# 03-AD9546_EdgeConnections_EEPROM.net
KiCad netlist of a schematic drawn in Altium Designer
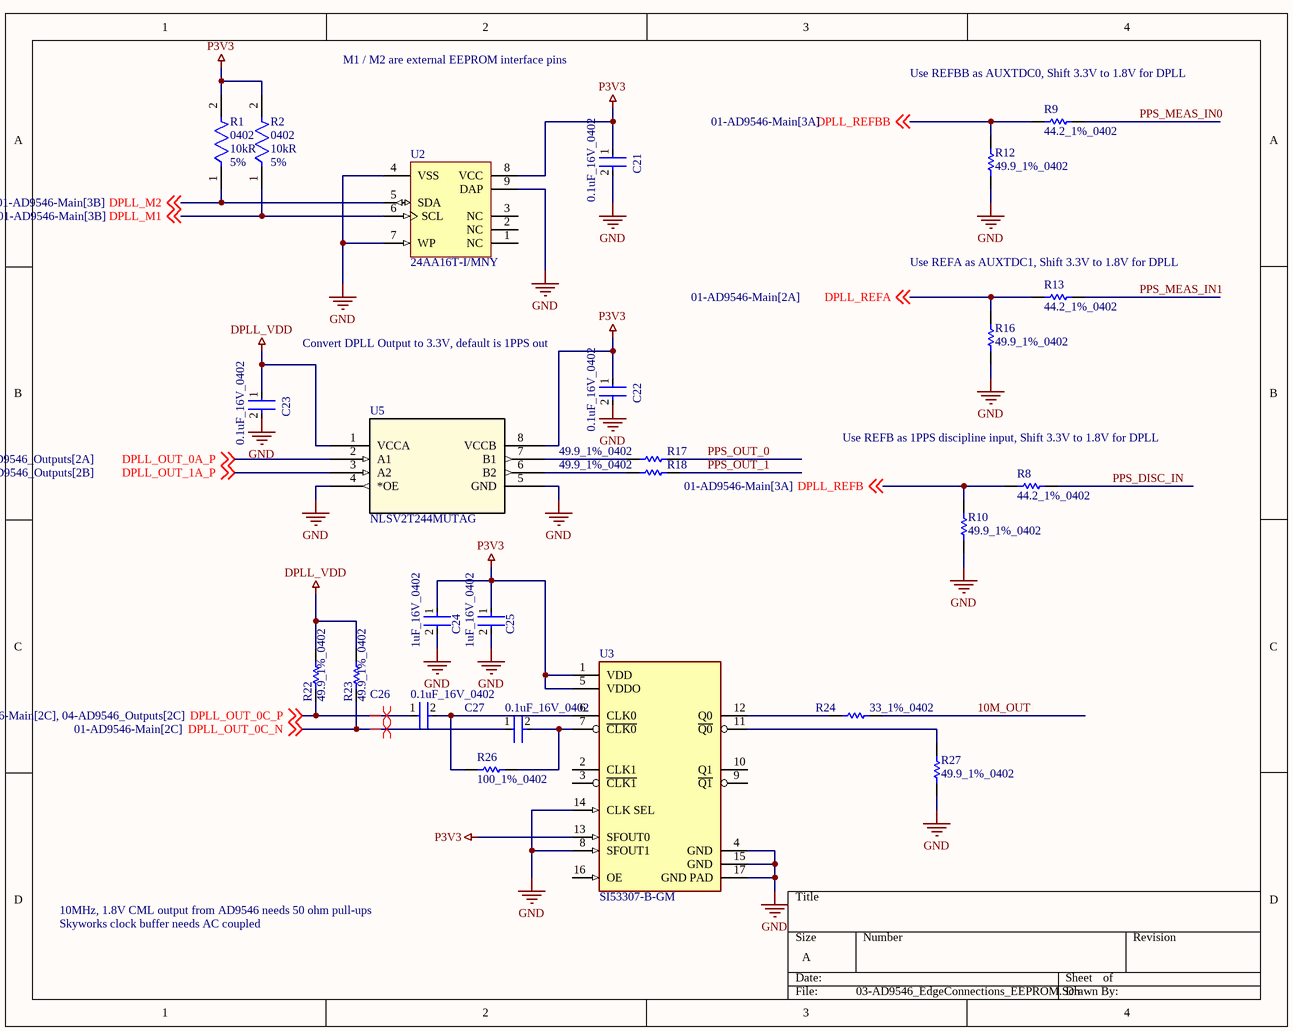
[diagram p0: 03-AD9546_EdgeConnections_EEPROM.SchDoc]

(export (version "E")
  (design (tool "Eeschema 10.0.6"))
  (components
    (comp (ref "C21")
      (value "0.1uF_16V_0402")
      (footprint "FP-GRM15-MFG")
      (description "CAP CER 0.1UF 16V X7R 0402")
      (fields (field (name "MANUFACTURER PART NUMBER") "GRM155R71C104KA88D") (field (name "TOLERANCE") "10%"))
      (libsource (lib "Altium Content Vault") (part "236180d848d6139a670b325ea6854c9"))
    )
    (comp (ref "C22")
      (value "0.1uF_16V_0402")
      (footprint "FP-GRM15-MFG")
      (description "CAP CER 0.1UF 16V X7R 0402")
      (fields (field (name "MANUFACTURER PART NUMBER") "GRM155R71C104KA88D") (field (name "TOLERANCE") "10%"))
      (libsource (lib "Altium Content Vault") (part "236180d848d6139a670b325ea6854c9"))
    )
    (comp (ref "C23")
      (value "0.1uF_16V_0402")
      (footprint "FP-GRM15-MFG")
      (description "CAP CER 0.1UF 16V X7R 0402")
      (fields (field (name "MANUFACTURER PART NUMBER") "GRM155R71C104KA88D") (field (name "TOLERANCE") "10%"))
      (libsource (lib "Altium Content Vault") (part "236180d848d6139a670b325ea6854c9"))
    )
    (comp (ref "C24")
      (value "1uF_16V_0402")
      (footprint "FP-0402-L_1_0_0_05-W_0_5-IPC_C")
      (description "None")
      (fields (field (name "TOLERANCE") "20%") (field (name "VOLTAGE") "16V"))
      (libsource (lib "Altium Content Vault") (part "b4654b650e69147ec39a6b967a45e02"))
    )
    (comp (ref "C25")
      (value "1uF_16V_0402")
      (footprint "FP-0402-L_1_0_0_05-W_0_5-IPC_C")
      (description "None")
      (fields (field (name "TOLERANCE") "20%") (field (name "VOLTAGE") "16V"))
      (libsource (lib "Altium Content Vault") (part "b4654b650e69147ec39a6b967a45e02"))
    )
    (comp (ref "C26")
      (value "0.1uF_16V_0402")
      (footprint "FP-GRM15-MFG")
      (description "CAP CER 0.1UF 16V X7R 0402")
      (fields (field (name "MANUFACTURER PART NUMBER") "GRM155R71C104KA88D") (field (name "TOLERANCE") "10%"))
      (libsource (lib "Altium Content Vault") (part "236180d848d6139a670b325ea6854c9"))
    )
    (comp (ref "C27")
      (value "0.1uF_16V_0402")
      (footprint "FP-GRM15-MFG")
      (description "CAP CER 0.1UF 16V X7R 0402")
      (fields (field (name "MANUFACTURER PART NUMBER") "GRM155R71C104KA88D") (field (name "TOLERANCE") "10%"))
      (libsource (lib "Altium Content Vault") (part "236180d848d6139a670b325ea6854c9"))
    )
    (comp (ref "R1")
      (value "CRCW040210K0JNED")
      (footprint "FP-CRCW0402-e3-IPC_B")
      (description "RES Thick Film, 10kΩ, 5%, 0.063W, 200ppm/°C, 0402")
      (fields
        (field (name "CASE/PACKAGE") "0402")
        (field (name "RESISTANCE") "10kR")
        (field (name "TOLERANCE") "5%")
      )
      (libsource (lib "Altium Content Vault") (part "1029c3af85768c4190bb7ad29bc67b5"))
    )
    (comp (ref "R2")
      (value "CRCW040210K0JNED")
      (footprint "FP-CRCW0402-e3-IPC_B")
      (description "RES Thick Film, 10kΩ, 5%, 0.063W, 200ppm/°C, 0402")
      (fields
        (field (name "CASE/PACKAGE") "0402")
        (field (name "RESISTANCE") "10kR")
        (field (name "TOLERANCE") "5%")
      )
      (libsource (lib "Altium Content Vault") (part "1029c3af85768c4190bb7ad29bc67b5"))
    )
    (comp (ref "R8")
      (value "44.2_1%_0402")
      (footprint "RESC1005X40X25LL05T05")
      (fields (field (name "MANUFACTURER") "Vishay Dale") (field (name "PART NUMBER") "CRCW040244R2FKED"))
      (libsource (lib "Altium Content Vault") (part "RES"))
    )
    (comp (ref "R9")
      (value "44.2_1%_0402")
      (footprint "RESC1005X40X25LL05T05")
      (fields (field (name "MANUFACTURER") "Vishay Dale") (field (name "PART NUMBER") "CRCW040244R2FKED"))
      (libsource (lib "Altium Content Vault") (part "RES"))
    )
    (comp (ref "R10")
      (value "49.9_1%_0402")
      (footprint "RESC1005X40X25NL05T05")
      (fields (field (name "MANUFACTURER") "Panasonic") (field (name "PART NUMBER") "ERJ-2RKF49R9X"))
      (libsource (lib "Altium Content Vault") (part "RES"))
    )
    (comp (ref "R12")
      (value "49.9_1%_0402")
      (footprint "RESC1005X40X25NL05T05")
      (fields (field (name "MANUFACTURER") "Panasonic") (field (name "PART NUMBER") "ERJ-2RKF49R9X"))
      (libsource (lib "Altium Content Vault") (part "RES"))
    )
    (comp (ref "R13")
      (value "44.2_1%_0402")
      (footprint "RESC1005X40X25LL05T05")
      (fields (field (name "MANUFACTURER") "Vishay Dale") (field (name "PART NUMBER") "CRCW040244R2FKED"))
      (libsource (lib "Altium Content Vault") (part "RES"))
    )
    (comp (ref "R16")
      (value "49.9_1%_0402")
      (footprint "RESC1005X40X25NL05T05")
      (fields (field (name "MANUFACTURER") "Panasonic") (field (name "PART NUMBER") "ERJ-2RKF49R9X"))
      (libsource (lib "Altium Content Vault") (part "RES"))
    )
    (comp (ref "R17")
      (value "49.9_1%_0402")
      (footprint "RESC1005X40X25NL05T05")
      (fields (field (name "MANUFACTURER") "Panasonic") (field (name "PART NUMBER") "ERJ-2RKF49R9X"))
      (libsource (lib "Altium Content Vault") (part "RES"))
    )
    (comp (ref "R18")
      (value "49.9_1%_0402")
      (footprint "RESC1005X40X25NL05T05")
      (fields (field (name "MANUFACTURER") "Panasonic") (field (name "PART NUMBER") "ERJ-2RKF49R9X"))
      (libsource (lib "Altium Content Vault") (part "RES"))
    )
    (comp (ref "R22")
      (value "49.9_1%_0402")
      (footprint "RESC1005X40X25NL05T05")
      (fields (field (name "MANUFACTURER") "Panasonic") (field (name "PART NUMBER") "ERJ-2RKF49R9X"))
      (libsource (lib "Altium Content Vault") (part "RES"))
    )
    (comp (ref "R23")
      (value "49.9_1%_0402")
      (footprint "RESC1005X40X25NL05T05")
      (fields (field (name "MANUFACTURER") "Panasonic") (field (name "PART NUMBER") "ERJ-2RKF49R9X"))
      (libsource (lib "Altium Content Vault") (part "RES"))
    )
    (comp (ref "R24")
      (value "33_1%_0402")
      (footprint "RESC1005X40X25LL05T10")
      (fields (field (name "PART NUMBER") "RC0402FR-0733RL") (field (name "MANUFACTURER") "Yageo / Phycomp"))
      (libsource (lib "Altium Content Vault") (part "RES"))
    )
    (comp (ref "R26")
      (value "100_1%_0402")
      (footprint "RESC1005X40X25ML05T10")
      (fields (field (name "PART NUMBER") "RC0402FR-07100RL") (field (name "MANUFACTURER") "Yageo / Phycomp"))
      (libsource (lib "Altium Content Vault") (part "RES"))
    )
    (comp (ref "R27")
      (value "49.9_1%_0402")
      (footprint "RESC1005X40X25NL05T05")
      (fields (field (name "MANUFACTURER") "Panasonic") (field (name "PART NUMBER") "ERJ-2RKF49R9X"))
      (libsource (lib "Altium Content Vault") (part "RES"))
    )
    (comp (ref "U2")
      (value "24AA16T-I/MNY")
      (footprint "TDFN-MN8")
      (libsource (lib "Altium Content Vault") (part "MEM-SEEPROM-24AA08-IL9"))
    )
    (comp (ref "U3")
      (value "SI53307-B-GM")
      (footprint "FP-SI53307-B-GM-MFG")
      (description "Clock Fanout Buffer (Distribution), Multiplexer IC 2:4 725MHz 16-VFQFN Exposed Pad")
      (fields (field (name "OCTOPART") "https://octopart.com/si53307-b-gm-silicon+labs-51374320"))
      (libsource (lib "Altium Content Vault") (part "8366162297a72c4edb5e5ae86e4b614"))
    )
    (comp (ref "U5")
      (value "NLSV2T244MUTAG")
      (footprint "UDFN8_1P20X1P80_ONS")
      (description "No Description Available")
      (fields (field (name "COPYRIGHT") "Copyright (C) 2023 Ultra Librarian. All rights reserved."))
      (libsource (lib "NLSV2T244MUTAG") (part "NLSV2T244MUTAG"))
    )
  )
  (nets
    (net (code "1") (name "/10M_OUT") (class "Default")
      (node (ref "R24") (pin "2") (pinfunction "2_2") (pintype "passive"))
    )
    (net (code "2") (name "/PPS_DISC_IN") (class "Default")
      (node (ref "R8") (pin "2") (pinfunction "2_2") (pintype "passive"))
    )
    (net (code "3") (name "/PPS_MEAS_IN0") (class "Default")
      (node (ref "R9") (pin "2") (pinfunction "2_2") (pintype "passive"))
    )
    (net (code "4") (name "/PPS_MEAS_IN1") (class "Default")
      (node (ref "R13") (pin "2") (pinfunction "2_2") (pintype "passive"))
    )
    (net (code "5") (name "/PPS_OUT_0") (class "Default")
      (node (ref "R17") (pin "1") (pinfunction "1_1") (pintype "passive"))
    )
    (net (code "6") (name "/PPS_OUT_1") (class "Default")
      (node (ref "R18") (pin "1") (pinfunction "1_1") (pintype "passive"))
    )
    (net (code "7") (name "DPLL_M1") (class "Default")
      (node (ref "R2") (pin "1") (pinfunction "1_1") (pintype "passive"))
      (node (ref "U2") (pin "6") (pinfunction "SCL_6") (pintype "input"))
    )
    (net (code "8") (name "DPLL_M2") (class "Default")
      (node (ref "R1") (pin "1") (pinfunction "1_1") (pintype "passive"))
      (node (ref "U2") (pin "5") (pinfunction "SDA_5") (pintype "bidirectional"))
    )
    (net (code "9") (name "DPLL_OUT_0A_P") (class "Default")
      (node (ref "U5") (pin "2") (pinfunction "A1_2") (pintype "input"))
    )
    (net (code "10") (name "DPLL_OUT_0C_N") (class "Default")
      (node (ref "C27") (pin "1") (pinfunction "1_1") (pintype "passive"))
      (node (ref "R23") (pin "2") (pinfunction "2_2") (pintype "passive"))
    )
    (net (code "11") (name "DPLL_OUT_0C_P") (class "Default")
      (node (ref "C26") (pin "1") (pinfunction "1_1") (pintype "passive"))
      (node (ref "R22") (pin "2") (pinfunction "2_2") (pintype "passive"))
    )
    (net (code "12") (name "DPLL_OUT_1A_P") (class "Default")
      (node (ref "U5") (pin "3") (pinfunction "A2_3") (pintype "input"))
    )
    (net (code "13") (name "DPLL_REFA") (class "Default")
      (node (ref "R13") (pin "1") (pinfunction "1_1") (pintype "passive"))
      (node (ref "R16") (pin "2") (pinfunction "2_2") (pintype "passive"))
    )
    (net (code "14") (name "DPLL_REFB") (class "Default")
      (node (ref "R10") (pin "2") (pinfunction "2_2") (pintype "passive"))
      (node (ref "R8") (pin "1") (pinfunction "1_1") (pintype "passive"))
    )
    (net (code "15") (name "DPLL_REFBB") (class "Default")
      (node (ref "R12") (pin "2") (pinfunction "2_2") (pintype "passive"))
      (node (ref "R9") (pin "1") (pinfunction "1_1") (pintype "passive"))
    )
    (net (code "16") (name "DPLL_VDD") (class "Default")
      (node (ref "C23") (pin "1") (pinfunction "1_1") (pintype "passive"))
      (node (ref "R22") (pin "1") (pinfunction "1_1") (pintype "passive"))
      (node (ref "R23") (pin "1") (pinfunction "1_1") (pintype "passive"))
      (node (ref "U5") (pin "1") (pinfunction "VCCA_1") (pintype "power_in"))
    )
    (net (code "17") (name "GND") (class "Default")
      (node (ref "C21") (pin "2") (pinfunction "2_2") (pintype "passive"))
      (node (ref "C22") (pin "2") (pinfunction "2_2") (pintype "passive"))
      (node (ref "C23") (pin "2") (pinfunction "2_2") (pintype "passive"))
      (node (ref "C24") (pin "2") (pinfunction "2_2") (pintype "passive"))
      (node (ref "C25") (pin "2") (pinfunction "2_2") (pintype "passive"))
      (node (ref "R10") (pin "1") (pinfunction "1_1") (pintype "passive"))
      (node (ref "R12") (pin "1") (pinfunction "1_1") (pintype "passive"))
      (node (ref "R16") (pin "1") (pinfunction "1_1") (pintype "passive"))
      (node (ref "R27") (pin "2") (pinfunction "2_2") (pintype "passive"))
      (node (ref "U2") (pin "4") (pinfunction "VSS_4") (pintype "power_in"))
      (node (ref "U2") (pin "7") (pinfunction "WP_7") (pintype "input"))
      (node (ref "U2") (pin "9") (pinfunction "DAP_9") (pintype "power_in"))
      (node (ref "U3") (pin "14") (pinfunction "CLK_SEL_14") (pintype "input"))
      (node (ref "U3") (pin "15") (pinfunction "GND_15") (pintype "power_in"))
      (node (ref "U3") (pin "17") (pinfunction "GND_PAD_17") (pintype "power_in"))
      (node (ref "U3") (pin "4") (pinfunction "GND_4") (pintype "power_in"))
      (node (ref "U3") (pin "8") (pinfunction "SFOUT1_8") (pintype "input"))
      (node (ref "U5") (pin "4") (pinfunction "*OE_4") (pintype "output"))
      (node (ref "U5") (pin "5") (pinfunction "GND_5") (pintype "power_in"))
    )
    (net (code "18") (name "Net-(U3-CLK0)") (class "Default")
      (node (ref "C26") (pin "2") (pinfunction "2_2") (pintype "passive"))
      (node (ref "R26") (pin "1") (pinfunction "1_1") (pintype "passive"))
      (node (ref "U3") (pin "6") (pinfunction "CLK0_6") (pintype "passive"))
    )
    (net (code "19") (name "Net-(U3-Q0)") (class "Default")
      (node (ref "R24") (pin "1") (pinfunction "1_1") (pintype "passive"))
      (node (ref "U3") (pin "12") (pinfunction "Q0_12") (pintype "passive"))
    )
    (net (code "20") (name "Net-(U3-~{CLK0})") (class "Default")
      (node (ref "C27") (pin "2") (pinfunction "2_2") (pintype "passive"))
      (node (ref "R26") (pin "2") (pinfunction "2_2") (pintype "passive"))
      (node (ref "U3") (pin "7") (pinfunction "~{CLK0}_7") (pintype "passive"))
    )
    (net (code "21") (name "Net-(U3-~{Q0})") (class "Default")
      (node (ref "R27") (pin "1") (pinfunction "1_1") (pintype "passive"))
      (node (ref "U3") (pin "11") (pinfunction "~{Q0}_11") (pintype "passive"))
    )
    (net (code "22") (name "Net-(U5-B1)") (class "Default")
      (node (ref "R17") (pin "2") (pinfunction "2_2") (pintype "passive"))
      (node (ref "U5") (pin "7") (pinfunction "B1_7") (pintype "output"))
    )
    (net (code "23") (name "Net-(U5-B2)") (class "Default")
      (node (ref "R18") (pin "2") (pinfunction "2_2") (pintype "passive"))
      (node (ref "U5") (pin "6") (pinfunction "B2_6") (pintype "output"))
    )
    (net (code "24") (name "P3V3") (class "Default")
      (node (ref "C21") (pin "1") (pinfunction "1_1") (pintype "passive"))
      (node (ref "C22") (pin "1") (pinfunction "1_1") (pintype "passive"))
      (node (ref "C24") (pin "1") (pinfunction "1_1") (pintype "passive"))
      (node (ref "C25") (pin "1") (pinfunction "1_1") (pintype "passive"))
      (node (ref "R1") (pin "2") (pinfunction "2_2") (pintype "passive"))
      (node (ref "R2") (pin "2") (pinfunction "2_2") (pintype "passive"))
      (node (ref "U2") (pin "8") (pinfunction "VCC_8") (pintype "power_in"))
      (node (ref "U3") (pin "1") (pinfunction "VDD_1") (pintype "power_in"))
      (node (ref "U3") (pin "13") (pinfunction "SFOUT0_13") (pintype "input"))
      (node (ref "U3") (pin "5") (pinfunction "VDDO_5") (pintype "power_in"))
      (node (ref "U5") (pin "8") (pinfunction "VCCB_8") (pintype "power_in"))
    )
    (net (code "25") (name "unconnected-(U2-NC-Pad1)") (class "Default")
      (node (ref "U2") (pin "1") (pinfunction "NC_1") (pintype "passive"))
    )
    (net (code "26") (name "unconnected-(U2-NC-Pad2)") (class "Default")
      (node (ref "U2") (pin "2") (pinfunction "NC_2") (pintype "passive"))
    )
    (net (code "27") (name "unconnected-(U2-NC-Pad3)") (class "Default")
      (node (ref "U2") (pin "3") (pinfunction "NC_3") (pintype "passive"))
    )
    (net (code "28") (name "unconnected-(U3-CLK1-Pad2)") (class "Default")
      (node (ref "U3") (pin "2") (pinfunction "CLK1_2") (pintype "passive"))
    )
    (net (code "29") (name "unconnected-(U3-OE-Pad16)") (class "Default")
      (node (ref "U3") (pin "16") (pinfunction "OE_16") (pintype "input"))
    )
    (net (code "30") (name "unconnected-(U3-Q1-Pad10)") (class "Default")
      (node (ref "U3") (pin "10") (pinfunction "Q1_10") (pintype "passive"))
    )
    (net (code "31") (name "unconnected-(U3-~{CLK1}-Pad3)") (class "Default")
      (node (ref "U3") (pin "3") (pinfunction "~{CLK1}_3") (pintype "passive"))
    )
    (net (code "32") (name "unconnected-(U3-~{Q1}-Pad9)") (class "Default")
      (node (ref "U3") (pin "9") (pinfunction "~{Q1}_9") (pintype "passive"))
    )
  )
)
